# V2.net
KiCad netlist of a schematic drawn in EAGLE
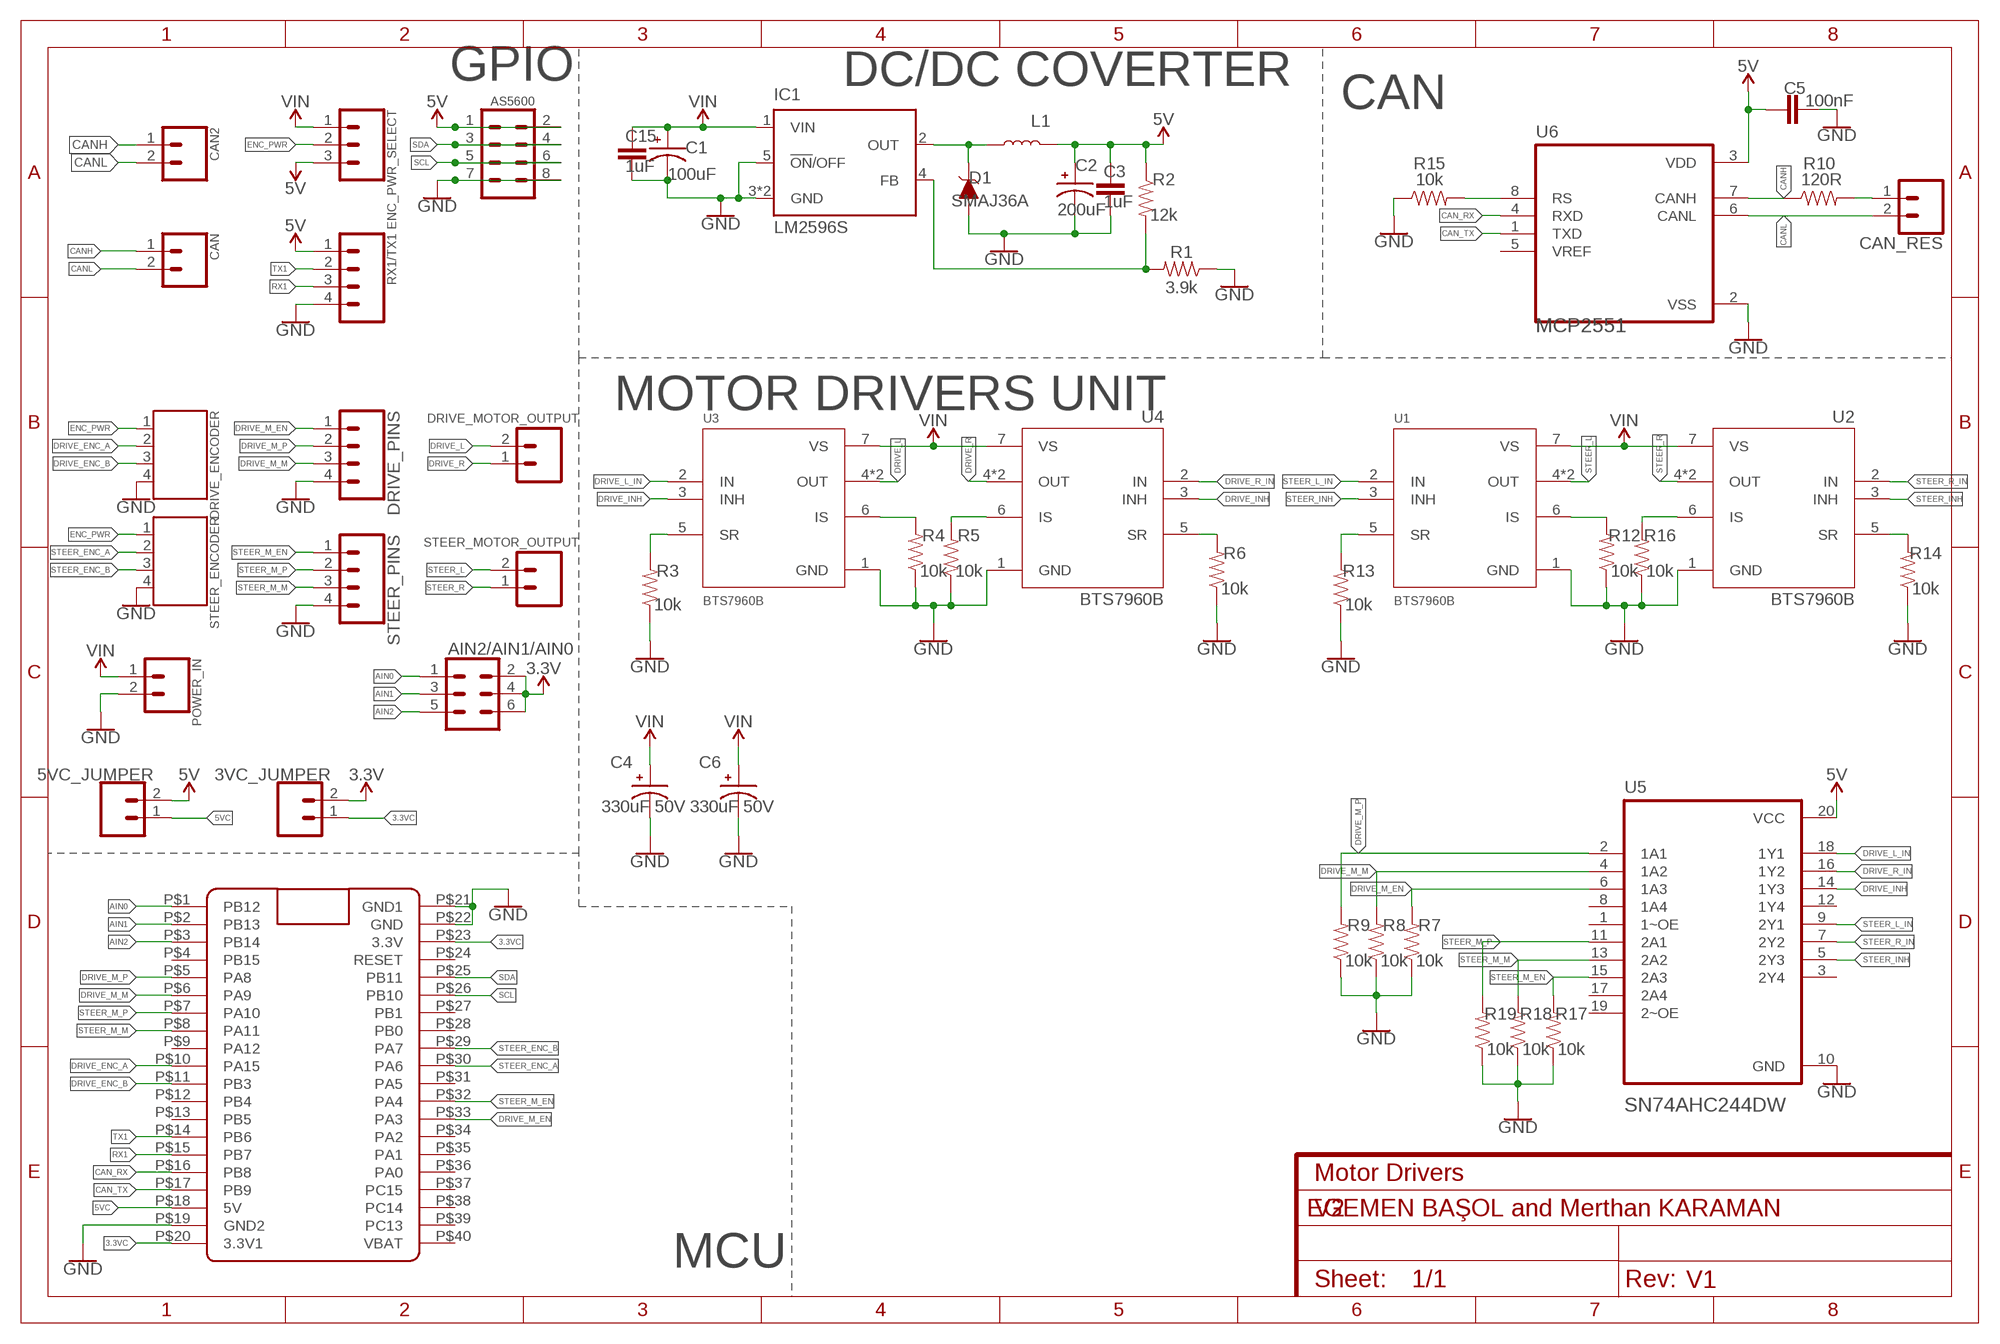
[diagram p0: schematic, sheet 1]

(export (version "E")
  (design (tool "Eeschema 10.0.6"))
  (components
    (comp (ref "3VC_JUMPER")
      (value "CONN_02")
      (footprint "eagle-import:1X02")
      (libsource (lib "eagle-import") (part "CONN_02"))
    )
    (comp (ref "5VC_JUMPER")
      (value "CONN_02")
      (footprint "eagle-import:1X02")
      (libsource (lib "eagle-import") (part "CONN_02"))
    )
    (comp (ref "AIN2/AIN1/AIN0")
      (value "CONN_03X2FEMALE")
      (footprint "eagle-import:2X3")
      (libsource (lib "eagle-import") (part "CONN_03X2FEMALE"))
    )
    (comp (ref "AS5600")
      (value "5V/SCL/SDA/GND")
      (footprint "eagle-import:2X4")
      (libsource (lib "eagle-import") (part "CONN_04X2"))
    )
    (comp (ref "C1")
      (value "100uF")
      (footprint "eagle-import:CPOL-SMD")
      (fields (field (name "MF") "Panasonic") (field (name "MP") "EEEFN1H101L"))
      (libsource (lib "eagle-import") (part "CPOL-SMD"))
    )
    (comp (ref "C2")
      (value "200uF")
      (footprint "eagle-import:CPOL-SMD")
      (fields (field (name "MF") "Panasonic") (field (name "MP") "EEEFN1H101L"))
      (libsource (lib "eagle-import") (part "CPOL-SMD"))
    )
    (comp (ref "C3")
      (value "1uF")
      (footprint "eagle-import:0603")
      (libsource (lib "eagle-import") (part "0.18UF-0603-10V-10%"))
    )
    (comp (ref "C4")
      (value "330uF 50V")
      (footprint "eagle-import:CPOL-RADIAL-5MM-10MM")
      (fields (field (name "MF") "Panasonic") (field (name "MP") "ECA2VM4R7"))
      (libsource (lib "eagle-import") (part "CPOL-RADIAL-5MM-10MM"))
    )
    (comp (ref "C5")
      (value "100nF")
      (footprint "eagle-import:0805")
      (libsource (lib "eagle-import") (part "CAP-0805"))
    )
    (comp (ref "C6")
      (value "330uF 50V")
      (footprint "eagle-import:CPOL-RADIAL-5MM-10MM")
      (fields (field (name "MF") "Panasonic") (field (name "MP") "ECA2VM4R7"))
      (libsource (lib "eagle-import") (part "CPOL-RADIAL-5MM-10MM"))
    )
    (comp (ref "C15")
      (value "1uF")
      (footprint "eagle-import:0805")
      (libsource (lib "eagle-import") (part "2.2UF-0805-25V-(+80/-20%)"))
    )
    (comp (ref "CAN")
      (value "CANH/CANL")
      (footprint "eagle-import:5.08MM_2PIN")
      (libsource (lib "eagle-import") (part "5.08MM_2PIN"))
    )
    (comp (ref "CAN2")
      (value "CANH/CANL")
      (footprint "eagle-import:5.08MM_2PIN")
      (libsource (lib "eagle-import") (part "5.08MM_2PIN"))
    )
    (comp (ref "CAN_RES")
      (value "CONN_02")
      (footprint "eagle-import:1X02")
      (libsource (lib "eagle-import") (part "CONN_02"))
    )
    (comp (ref "D1")
      (value "SMAJ36A")
      (footprint "eagle-import:DO-214AC")
      (libsource (lib "eagle-import") (part "DIODE_TVS_UNI"))
    )
    (comp (ref "DRIVE_ENCODER")
      (value "GND/B/A/PWR")
      (footprint "eagle-import:5.08MM_4PIN")
      (fields (field (name "MF") "CUI Devices") (field (name "MP") "TB006-508-04BE"))
      (libsource (lib "eagle-import") (part "5.08MM_4PIN"))
    )
    (comp (ref "DRIVE_MOTOR_OUTPUT")
      (value "5.08MM_2PIN")
      (footprint "eagle-import:5.08MM_2PIN")
      (libsource (lib "eagle-import") (part "5.08MM_2PIN"))
    )
    (comp (ref "DRIVE_PINS")
      (value "EN/ PWM_P/ PWM_M/ GND")
      (footprint "eagle-import:1X04")
      (libsource (lib "eagle-import") (part "CONN_04"))
    )
    (comp (ref "ENC_PWR_SELECT")
      (value "VIN/PWR/5V")
      (footprint "eagle-import:1X03")
      (libsource (lib "eagle-import") (part "CONN_03"))
    )
    (comp (ref "IC1")
      (value "LM2596S")
      (footprint "eagle-import:TO263-5")
      (libsource (lib "eagle-import") (part "LM2596S"))
    )
    (comp (ref "L1")
      (value "47uH")
      (footprint "eagle-import:COIL_14X14")
      (libsource (lib "eagle-import") (part "COIL"))
    )
    (comp (ref "POWER_IN")
      (value "VIN/GND")
      (footprint "eagle-import:5.08MM_2PIN")
      (libsource (lib "eagle-import") (part "5.08MM_2PIN"))
    )
    (comp (ref "R1")
      (value "3.9k")
      (footprint "eagle-import:0805")
      (libsource (lib "eagle-import") (part "RESISTOR0805"))
    )
    (comp (ref "R2")
      (value "12k")
      (footprint "eagle-import:0805")
      (libsource (lib "eagle-import") (part "RESISTOR0805"))
    )
    (comp (ref "R3")
      (value "10k")
      (footprint "eagle-import:0805")
      (libsource (lib "eagle-import") (part "RESISTOR0805"))
    )
    (comp (ref "R4")
      (value "10k")
      (footprint "eagle-import:0805")
      (libsource (lib "eagle-import") (part "RESISTOR0805"))
    )
    (comp (ref "R5")
      (value "10k")
      (footprint "eagle-import:0805")
      (libsource (lib "eagle-import") (part "RESISTOR0805"))
    )
    (comp (ref "R6")
      (value "10k")
      (footprint "eagle-import:0805")
      (libsource (lib "eagle-import") (part "RESISTOR0805"))
    )
    (comp (ref "R7")
      (value "10k")
      (footprint "eagle-import:0805")
      (libsource (lib "eagle-import") (part "RESISTOR0805"))
    )
    (comp (ref "R8")
      (value "10k")
      (footprint "eagle-import:0805")
      (libsource (lib "eagle-import") (part "RESISTOR0805"))
    )
    (comp (ref "R9")
      (value "10k")
      (footprint "eagle-import:0805")
      (libsource (lib "eagle-import") (part "RESISTOR0805"))
    )
    (comp (ref "R10")
      (value "120R")
      (footprint "eagle-import:0805")
      (libsource (lib "eagle-import") (part "RESISTOR0805"))
    )
    (comp (ref "R12")
      (value "10k")
      (footprint "eagle-import:0805")
      (libsource (lib "eagle-import") (part "RESISTOR0805"))
    )
    (comp (ref "R13")
      (value "10k")
      (footprint "eagle-import:0805")
      (libsource (lib "eagle-import") (part "RESISTOR0805"))
    )
    (comp (ref "R14")
      (value "10k")
      (footprint "eagle-import:0805")
      (libsource (lib "eagle-import") (part "RESISTOR0805"))
    )
    (comp (ref "R15")
      (value "10k")
      (footprint "eagle-import:0805")
      (libsource (lib "eagle-import") (part "RESISTOR0805"))
    )
    (comp (ref "R16")
      (value "10k")
      (footprint "eagle-import:0805")
      (libsource (lib "eagle-import") (part "RESISTOR0805"))
    )
    (comp (ref "R17")
      (value "10k")
      (footprint "eagle-import:0805")
      (libsource (lib "eagle-import") (part "RESISTOR0805"))
    )
    (comp (ref "R18")
      (value "10k")
      (footprint "eagle-import:0805")
      (libsource (lib "eagle-import") (part "RESISTOR0805"))
    )
    (comp (ref "R19")
      (value "10k")
      (footprint "eagle-import:0805")
      (libsource (lib "eagle-import") (part "RESISTOR0805"))
    )
    (comp (ref "RX1/TX1")
      (value "GND/RX1/TX1/5V")
      (footprint "eagle-import:1X04")
      (libsource (lib "eagle-import") (part "CONN_04"))
    )
    (comp (ref "STEER_ENCODER")
      (value "PWR/A/B/GND")
      (footprint "eagle-import:5.08MM_4PIN")
      (fields (field (name "MF") "CUI Devices") (field (name "MP") "TB006-508-04BE"))
      (libsource (lib "eagle-import") (part "5.08MM_4PIN"))
    )
    (comp (ref "STEER_MOTOR_OUTPUT")
      (value "5.08MM_2PIN")
      (footprint "eagle-import:5.08MM_2PIN")
      (libsource (lib "eagle-import") (part "5.08MM_2PIN"))
    )
    (comp (ref "STEER_PINS")
      (value "EN/ PWM_P/ PWM_M/ GND")
      (footprint "eagle-import:1X04")
      (libsource (lib "eagle-import") (part "CONN_04"))
    )
    (comp (ref "U$1")
      (value "BLUE_PILL")
      (footprint "eagle-import:BLUE_PILL")
      (libsource (lib "eagle-import") (part "BLUE_PILL"))
    )
    (comp (ref "U1")
      (value "BTS7960B")
      (footprint "eagle-import:DPAK127P1490X440-8N")
      (libsource (lib "eagle-import") (part "BTS7960B"))
    )
    (comp (ref "U2")
      (value "BTS7960B")
      (footprint "eagle-import:DPAK127P1490X440-8N")
      (libsource (lib "eagle-import") (part "BTS7960B"))
    )
    (comp (ref "U3")
      (value "BTS7960B")
      (footprint "eagle-import:DPAK127P1490X440-8N")
      (libsource (lib "eagle-import") (part "BTS7960B"))
    )
    (comp (ref "U4")
      (value "BTS7960B")
      (footprint "eagle-import:DPAK127P1490X440-8N")
      (libsource (lib "eagle-import") (part "BTS7960B"))
    )
    (comp (ref "U5")
      (value "SN74AHC244DW")
      (footprint "eagle-import:SOIC127P1030X265-20N")
      (fields (field (name "MF") "Texas Instruments"))
      (libsource (lib "eagle-import") (part "SN74AHC244DW"))
    )
    (comp (ref "U6")
      (value "MCP2551")
      (footprint "eagle-import:DIP-8")
      (fields (field (name "MF") "Microchip") (field (name "MP") "MCP2551-E/P"))
      (libsource (lib "eagle-import") (part "MCP2551"))
    )
  )
  (nets
    (net (code "1") (name "3.3V") (class "Default")
      (node (ref "3VC_JUMPER") (pin "2") (pinfunction "2_2") (pintype "passive"))
      (node (ref "AIN2/AIN1/AIN0") (pin "2") (pinfunction "2_2") (pintype "bidirectional"))
      (node (ref "AIN2/AIN1/AIN0") (pin "4") (pinfunction "4_4") (pintype "bidirectional"))
      (node (ref "AIN2/AIN1/AIN0") (pin "6") (pinfunction "6_6") (pintype "bidirectional"))
    )
    (net (code "2") (name "3.3VC") (class "Default")
      (node (ref "3VC_JUMPER") (pin "1") (pinfunction "1_1") (pintype "passive"))
      (node (ref "U$1") (pin "P$20") (pinfunction "3.3V1_P$20") (pintype "bidirectional"))
      (node (ref "U$1") (pin "P$23") (pinfunction "3.3V_P$23") (pintype "bidirectional"))
    )
    (net (code "3") (name "5V") (class "Default")
      (node (ref "5VC_JUMPER") (pin "2") (pinfunction "2_2") (pintype "passive"))
      (node (ref "AS5600") (pin "1") (pinfunction "1_1") (pintype "passive"))
      (node (ref "AS5600") (pin "2") (pinfunction "2_2") (pintype "passive"))
      (node (ref "C2") (pin "1") (pinfunction "1_1") (pintype "passive"))
      (node (ref "C3") (pin "2") (pinfunction "2_2") (pintype "passive"))
      (node (ref "C5") (pin "2") (pinfunction "2_2") (pintype "passive"))
      (node (ref "ENC_PWR_SELECT") (pin "3") (pinfunction "3_3") (pintype "passive"))
      (node (ref "L1") (pin "P$2") (pinfunction "2_P$2") (pintype "passive"))
      (node (ref "R2") (pin "1") (pinfunction "1_1") (pintype "passive"))
      (node (ref "RX1/TX1") (pin "1") (pinfunction "1_1") (pintype "passive"))
      (node (ref "U5") (pin "20") (pinfunction "VCC_20") (pintype "power_in"))
      (node (ref "U6") (pin "3") (pinfunction "VDD_3") (pintype "power_in"))
    )
    (net (code "4") (name "5VC") (class "Default")
      (node (ref "5VC_JUMPER") (pin "1") (pinfunction "1_1") (pintype "passive"))
      (node (ref "U$1") (pin "P$18") (pinfunction "5V_P$18") (pintype "bidirectional"))
    )
    (net (code "5") (name "AIN0") (class "Default")
      (node (ref "AIN2/AIN1/AIN0") (pin "1") (pinfunction "1_1") (pintype "bidirectional"))
      (node (ref "U$1") (pin "P$1") (pinfunction "PB12_P$1") (pintype "bidirectional"))
    )
    (net (code "6") (name "AIN1") (class "Default")
      (node (ref "AIN2/AIN1/AIN0") (pin "3") (pinfunction "3_3") (pintype "bidirectional"))
      (node (ref "U$1") (pin "P$2") (pinfunction "PB13_P$2") (pintype "bidirectional"))
    )
    (net (code "7") (name "AIN2") (class "Default")
      (node (ref "AIN2/AIN1/AIN0") (pin "5") (pinfunction "5_5") (pintype "bidirectional"))
      (node (ref "U$1") (pin "P$3") (pinfunction "PB14_P$3") (pintype "bidirectional"))
    )
    (net (code "8") (name "CANH") (class "Default")
      (node (ref "CAN") (pin "1") (pinfunction "1_1") (pintype "passive"))
      (node (ref "CAN2") (pin "1") (pinfunction "1_1") (pintype "passive"))
      (node (ref "R10") (pin "1") (pinfunction "1_1") (pintype "passive"))
      (node (ref "U6") (pin "7") (pinfunction "CANH_7") (pintype "output"))
    )
    (net (code "9") (name "CANL") (class "Default")
      (node (ref "CAN") (pin "2") (pinfunction "2_2") (pintype "passive"))
      (node (ref "CAN2") (pin "2") (pinfunction "2_2") (pintype "passive"))
      (node (ref "CAN_RES") (pin "2") (pinfunction "2_2") (pintype "passive"))
      (node (ref "U6") (pin "6") (pinfunction "CANL_6") (pintype "output"))
    )
    (net (code "10") (name "CAN_RX") (class "Default")
      (node (ref "U$1") (pin "P$16") (pinfunction "PB8_P$16") (pintype "bidirectional"))
      (node (ref "U6") (pin "4") (pinfunction "RXD_4") (pintype "input"))
    )
    (net (code "11") (name "CAN_TX") (class "Default")
      (node (ref "U$1") (pin "P$17") (pinfunction "PB9_P$17") (pintype "bidirectional"))
      (node (ref "U6") (pin "1") (pinfunction "TXD_1") (pintype "input"))
    )
    (net (code "12") (name "DRIVE_ENC_A") (class "Default")
      (node (ref "DRIVE_ENCODER") (pin "2") (pinfunction "2_2") (pintype "passive"))
      (node (ref "U$1") (pin "P$10") (pinfunction "PA15_P$10") (pintype "bidirectional"))
    )
    (net (code "13") (name "DRIVE_ENC_B") (class "Default")
      (node (ref "DRIVE_ENCODER") (pin "3") (pinfunction "3_3") (pintype "passive"))
      (node (ref "U$1") (pin "P$11") (pinfunction "PB3_P$11") (pintype "bidirectional"))
    )
    (net (code "14") (name "DRIVE_INH") (class "Default")
      (node (ref "U3") (pin "3") (pinfunction "INH_3") (pintype "input"))
      (node (ref "U4") (pin "3") (pinfunction "INH_3") (pintype "input"))
      (node (ref "U5") (pin "14") (pinfunction "1Y3_14") (pintype "output"))
    )
    (net (code "15") (name "DRIVE_L") (class "Default")
      (node (ref "DRIVE_MOTOR_OUTPUT") (pin "2") (pinfunction "2_2") (pintype "passive"))
      (node (ref "U3") (pin "4") (pinfunction "OUT_4") (pintype "output"))
      (node (ref "U3") (pin "8") (pinfunction "OUT_8") (pintype "output"))
    )
    (net (code "16") (name "DRIVE_L_IN") (class "Default")
      (node (ref "U3") (pin "2") (pinfunction "IN_2") (pintype "input"))
      (node (ref "U5") (pin "18") (pinfunction "1Y1_18") (pintype "output"))
    )
    (net (code "17") (name "DRIVE_M_EN") (class "Default")
      (node (ref "DRIVE_PINS") (pin "1") (pinfunction "1_1") (pintype "passive"))
      (node (ref "R7") (pin "2") (pinfunction "2_2") (pintype "passive"))
      (node (ref "U$1") (pin "P$33") (pinfunction "PA3_P$33") (pintype "bidirectional"))
      (node (ref "U5") (pin "6") (pinfunction "1A3_6") (pintype "input"))
    )
    (net (code "18") (name "DRIVE_M_M") (class "Default")
      (node (ref "DRIVE_PINS") (pin "3") (pinfunction "3_3") (pintype "passive"))
      (node (ref "R8") (pin "2") (pinfunction "2_2") (pintype "passive"))
      (node (ref "U$1") (pin "P$6") (pinfunction "PA9_P$6") (pintype "bidirectional"))
      (node (ref "U5") (pin "4") (pinfunction "1A2_4") (pintype "input"))
    )
    (net (code "19") (name "DRIVE_M_P") (class "Default")
      (node (ref "DRIVE_PINS") (pin "2") (pinfunction "2_2") (pintype "passive"))
      (node (ref "R9") (pin "2") (pinfunction "2_2") (pintype "passive"))
      (node (ref "U$1") (pin "P$5") (pinfunction "PA8_P$5") (pintype "bidirectional"))
      (node (ref "U5") (pin "2") (pinfunction "1A1_2") (pintype "input"))
    )
    (net (code "20") (name "DRIVE_R") (class "Default")
      (node (ref "DRIVE_MOTOR_OUTPUT") (pin "1") (pinfunction "1_1") (pintype "passive"))
      (node (ref "U4") (pin "4") (pinfunction "OUT_4") (pintype "output"))
      (node (ref "U4") (pin "8") (pinfunction "OUT_8") (pintype "output"))
    )
    (net (code "21") (name "DRIVE_R_IN") (class "Default")
      (node (ref "U4") (pin "2") (pinfunction "IN_2") (pintype "input"))
      (node (ref "U5") (pin "16") (pinfunction "1Y2_16") (pintype "output"))
    )
    (net (code "22") (name "ENC_PWR") (class "Default")
      (node (ref "DRIVE_ENCODER") (pin "1") (pinfunction "1_1") (pintype "passive"))
      (node (ref "ENC_PWR_SELECT") (pin "2") (pinfunction "2_2") (pintype "passive"))
      (node (ref "STEER_ENCODER") (pin "1") (pinfunction "1_1") (pintype "passive"))
    )
    (net (code "23") (name "GND") (class "Default")
      (node (ref "AS5600") (pin "7") (pinfunction "7_7") (pintype "passive"))
      (node (ref "AS5600") (pin "8") (pinfunction "8_8") (pintype "passive"))
      (node (ref "C1") (pin "2") (pinfunction "2_2") (pintype "passive"))
      (node (ref "C15") (pin "1") (pinfunction "1_1") (pintype "passive"))
      (node (ref "C2") (pin "2") (pinfunction "2_2") (pintype "passive"))
      (node (ref "C3") (pin "1") (pinfunction "1_1") (pintype "passive"))
      (node (ref "C4") (pin "N") (pinfunction "N_N") (pintype "passive"))
      (node (ref "C5") (pin "1") (pinfunction "1_1") (pintype "passive"))
      (node (ref "C6") (pin "N") (pinfunction "N_N") (pintype "passive"))
      (node (ref "D1") (pin "A") (pinfunction "A_A") (pintype "passive"))
      (node (ref "DRIVE_ENCODER") (pin "4") (pinfunction "4_4") (pintype "passive"))
      (node (ref "DRIVE_PINS") (pin "4") (pinfunction "4_4") (pintype "passive"))
      (node (ref "IC1") (pin "3") (pinfunction "GND_3") (pintype "power_in"))
      (node (ref "IC1") (pin "5") (pinfunction "~{ON}/OFF_5") (pintype "input"))
      (node (ref "IC1") (pin "TAB") (pinfunction "GND_TAB") (pintype "power_in"))
      (node (ref "POWER_IN") (pin "2") (pinfunction "2_2") (pintype "passive"))
      (node (ref "R1") (pin "1") (pinfunction "1_1") (pintype "passive"))
      (node (ref "R12") (pin "1") (pinfunction "1_1") (pintype "passive"))
      (node (ref "R13") (pin "1") (pinfunction "1_1") (pintype "passive"))
      (node (ref "R14") (pin "1") (pinfunction "1_1") (pintype "passive"))
      (node (ref "R15") (pin "1") (pinfunction "1_1") (pintype "passive"))
      (node (ref "R16") (pin "1") (pinfunction "1_1") (pintype "passive"))
      (node (ref "R17") (pin "1") (pinfunction "1_1") (pintype "passive"))
      (node (ref "R18") (pin "1") (pinfunction "1_1") (pintype "passive"))
      (node (ref "R19") (pin "1") (pinfunction "1_1") (pintype "passive"))
      (node (ref "R3") (pin "1") (pinfunction "1_1") (pintype "passive"))
      (node (ref "R4") (pin "1") (pinfunction "1_1") (pintype "passive"))
      (node (ref "R5") (pin "1") (pinfunction "1_1") (pintype "passive"))
      (node (ref "R6") (pin "1") (pinfunction "1_1") (pintype "passive"))
      (node (ref "R7") (pin "1") (pinfunction "1_1") (pintype "passive"))
      (node (ref "R8") (pin "1") (pinfunction "1_1") (pintype "passive"))
      (node (ref "R9") (pin "1") (pinfunction "1_1") (pintype "passive"))
      (node (ref "RX1/TX1") (pin "4") (pinfunction "4_4") (pintype "passive"))
      (node (ref "STEER_ENCODER") (pin "4") (pinfunction "4_4") (pintype "passive"))
      (node (ref "STEER_PINS") (pin "4") (pinfunction "4_4") (pintype "passive"))
      (node (ref "U$1") (pin "P$19") (pinfunction "GND2_P$19") (pintype "bidirectional"))
      (node (ref "U$1") (pin "P$21") (pinfunction "GND1_P$21") (pintype "power_in"))
      (node (ref "U$1") (pin "P$22") (pinfunction "GND_P$22") (pintype "bidirectional"))
      (node (ref "U1") (pin "1") (pinfunction "GND_1") (pintype "power_in"))
      (node (ref "U2") (pin "1") (pinfunction "GND_1") (pintype "power_in"))
      (node (ref "U3") (pin "1") (pinfunction "GND_1") (pintype "power_in"))
      (node (ref "U4") (pin "1") (pinfunction "GND_1") (pintype "power_in"))
      (node (ref "U5") (pin "10") (pinfunction "GND_10") (pintype "power_in"))
      (node (ref "U6") (pin "2") (pinfunction "VSS_2") (pintype "power_in"))
    )
    (net (code "24") (name "Net-(CAN_RES-Pad1)") (class "Default")
      (node (ref "CAN_RES") (pin "1") (pinfunction "1_1") (pintype "passive"))
      (node (ref "R10") (pin "2") (pinfunction "2_2") (pintype "passive"))
    )
    (net (code "25") (name "Net-(IC1-FB)") (class "Default")
      (node (ref "IC1") (pin "4") (pinfunction "FB_4") (pintype "input"))
      (node (ref "R1") (pin "2") (pinfunction "2_2") (pintype "passive"))
      (node (ref "R2") (pin "2") (pinfunction "2_2") (pintype "passive"))
    )
    (net (code "26") (name "Net-(IC1-OUT)") (class "Default")
      (node (ref "D1") (pin "C") (pinfunction "C_C") (pintype "passive"))
      (node (ref "IC1") (pin "2") (pinfunction "OUT_2") (pintype "output"))
      (node (ref "L1") (pin "P$1") (pinfunction "1_P$1") (pintype "passive"))
    )
    (net (code "27") (name "Net-(U1-IS)") (class "Default")
      (node (ref "R12") (pin "2") (pinfunction "2_2") (pintype "passive"))
      (node (ref "U1") (pin "6") (pinfunction "IS_6") (pintype "output"))
    )
    (net (code "28") (name "Net-(U1-SR)") (class "Default")
      (node (ref "R13") (pin "2") (pinfunction "2_2") (pintype "passive"))
      (node (ref "U1") (pin "5") (pinfunction "SR_5") (pintype "input"))
    )
    (net (code "29") (name "Net-(U2-IS)") (class "Default")
      (node (ref "R16") (pin "2") (pinfunction "2_2") (pintype "passive"))
      (node (ref "U2") (pin "6") (pinfunction "IS_6") (pintype "output"))
    )
    (net (code "30") (name "Net-(U2-SR)") (class "Default")
      (node (ref "R14") (pin "2") (pinfunction "2_2") (pintype "passive"))
      (node (ref "U2") (pin "5") (pinfunction "SR_5") (pintype "input"))
    )
    (net (code "31") (name "Net-(U3-IS)") (class "Default")
      (node (ref "R4") (pin "2") (pinfunction "2_2") (pintype "passive"))
      (node (ref "U3") (pin "6") (pinfunction "IS_6") (pintype "output"))
    )
    (net (code "32") (name "Net-(U3-SR)") (class "Default")
      (node (ref "R3") (pin "2") (pinfunction "2_2") (pintype "passive"))
      (node (ref "U3") (pin "5") (pinfunction "SR_5") (pintype "input"))
    )
    (net (code "33") (name "Net-(U4-IS)") (class "Default")
      (node (ref "R5") (pin "2") (pinfunction "2_2") (pintype "passive"))
      (node (ref "U4") (pin "6") (pinfunction "IS_6") (pintype "output"))
    )
    (net (code "34") (name "Net-(U4-SR)") (class "Default")
      (node (ref "R6") (pin "2") (pinfunction "2_2") (pintype "passive"))
      (node (ref "U4") (pin "5") (pinfunction "SR_5") (pintype "input"))
    )
    (net (code "35") (name "Net-(U6-RS)") (class "Default")
      (node (ref "R15") (pin "2") (pinfunction "2_2") (pintype "passive"))
      (node (ref "U6") (pin "8") (pinfunction "RS_8") (pintype "input"))
    )
    (net (code "36") (name "RX1") (class "Default")
      (node (ref "RX1/TX1") (pin "3") (pinfunction "3_3") (pintype "passive"))
      (node (ref "U$1") (pin "P$15") (pinfunction "PB7_P$15") (pintype "bidirectional"))
    )
    (net (code "37") (name "SCL") (class "Default")
      (node (ref "AS5600") (pin "5") (pinfunction "5_5") (pintype "passive"))
      (node (ref "AS5600") (pin "6") (pinfunction "6_6") (pintype "passive"))
      (node (ref "U$1") (pin "P$26") (pinfunction "PB10_P$26") (pintype "bidirectional"))
    )
    (net (code "38") (name "SDA") (class "Default")
      (node (ref "AS5600") (pin "3") (pinfunction "3_3") (pintype "passive"))
      (node (ref "AS5600") (pin "4") (pinfunction "4_4") (pintype "passive"))
      (node (ref "U$1") (pin "P$25") (pinfunction "PB11_P$25") (pintype "bidirectional"))
    )
    (net (code "39") (name "STEER_ENC_A") (class "Default")
      (node (ref "STEER_ENCODER") (pin "2") (pinfunction "2_2") (pintype "passive"))
      (node (ref "U$1") (pin "P$30") (pinfunction "PA6_P$30") (pintype "bidirectional"))
    )
    (net (code "40") (name "STEER_ENC_B") (class "Default")
      (node (ref "STEER_ENCODER") (pin "3") (pinfunction "3_3") (pintype "passive"))
      (node (ref "U$1") (pin "P$29") (pinfunction "PA7_P$29") (pintype "bidirectional"))
    )
    (net (code "41") (name "STEER_INH") (class "Default")
      (node (ref "U1") (pin "3") (pinfunction "INH_3") (pintype "input"))
      (node (ref "U2") (pin "3") (pinfunction "INH_3") (pintype "input"))
      (node (ref "U5") (pin "5") (pinfunction "2Y3_5") (pintype "output"))
    )
    (net (code "42") (name "STEER_L") (class "Default")
      (node (ref "STEER_MOTOR_OUTPUT") (pin "2") (pinfunction "2_2") (pintype "passive"))
      (node (ref "U1") (pin "4") (pinfunction "OUT_4") (pintype "output"))
      (node (ref "U1") (pin "8") (pinfunction "OUT_8") (pintype "output"))
    )
    (net (code "43") (name "STEER_L_IN") (class "Default")
      (node (ref "U1") (pin "2") (pinfunction "IN_2") (pintype "input"))
      (node (ref "U5") (pin "9") (pinfunction "2Y1_9") (pintype "output"))
    )
    (net (code "44") (name "STEER_M_EN") (class "Default")
      (node (ref "R17") (pin "2") (pinfunction "2_2") (pintype "passive"))
      (node (ref "STEER_PINS") (pin "1") (pinfunction "1_1") (pintype "passive"))
      (node (ref "U$1") (pin "P$32") (pinfunction "PA4_P$32") (pintype "bidirectional"))
      (node (ref "U5") (pin "15") (pinfunction "2A3_15") (pintype "input"))
    )
    (net (code "45") (name "STEER_M_M") (class "Default")
      (node (ref "R18") (pin "2") (pinfunction "2_2") (pintype "passive"))
      (node (ref "STEER_PINS") (pin "3") (pinfunction "3_3") (pintype "passive"))
      (node (ref "U$1") (pin "P$8") (pinfunction "PA11_P$8") (pintype "bidirectional"))
      (node (ref "U5") (pin "13") (pinfunction "2A2_13") (pintype "input"))
    )
    (net (code "46") (name "STEER_M_P") (class "Default")
      (node (ref "R19") (pin "2") (pinfunction "2_2") (pintype "passive"))
      (node (ref "STEER_PINS") (pin "2") (pinfunction "2_2") (pintype "passive"))
      (node (ref "U$1") (pin "P$7") (pinfunction "PA10_P$7") (pintype "bidirectional"))
      (node (ref "U5") (pin "11") (pinfunction "2A1_11") (pintype "input"))
    )
    (net (code "47") (name "STEER_R") (class "Default")
      (node (ref "STEER_MOTOR_OUTPUT") (pin "1") (pinfunction "1_1") (pintype "passive"))
      (node (ref "U2") (pin "4") (pinfunction "OUT_4") (pintype "output"))
      (node (ref "U2") (pin "8") (pinfunction "OUT_8") (pintype "output"))
    )
    (net (code "48") (name "STEER_R_IN") (class "Default")
      (node (ref "U2") (pin "2") (pinfunction "IN_2") (pintype "input"))
      (node (ref "U5") (pin "7") (pinfunction "2Y2_7") (pintype "output"))
    )
    (net (code "49") (name "TX1") (class "Default")
      (node (ref "RX1/TX1") (pin "2") (pinfunction "2_2") (pintype "passive"))
      (node (ref "U$1") (pin "P$14") (pinfunction "PB6_P$14") (pintype "bidirectional"))
    )
    (net (code "50") (name "VIN") (class "Default")
      (node (ref "C1") (pin "1") (pinfunction "1_1") (pintype "passive"))
      (node (ref "C15") (pin "2") (pinfunction "2_2") (pintype "passive"))
      (node (ref "C4") (pin "P") (pinfunction "P_P") (pintype "passive"))
      (node (ref "C6") (pin "P") (pinfunction "P_P") (pintype "passive"))
      (node (ref "ENC_PWR_SELECT") (pin "1") (pinfunction "1_1") (pintype "passive"))
      (node (ref "IC1") (pin "1") (pinfunction "VIN_1") (pintype "input"))
      (node (ref "POWER_IN") (pin "1") (pinfunction "1_1") (pintype "passive"))
      (node (ref "U1") (pin "7") (pinfunction "VS_7") (pintype "power_in"))
      (node (ref "U2") (pin "7") (pinfunction "VS_7") (pintype "power_in"))
      (node (ref "U3") (pin "7") (pinfunction "VS_7") (pintype "power_in"))
      (node (ref "U4") (pin "7") (pinfunction "VS_7") (pintype "power_in"))
    )
    (net (code "51") (name "unconnected-(U$1-PA0-PadP$36)") (class "Default")
      (node (ref "U$1") (pin "P$36") (pinfunction "PA0_P$36") (pintype "bidirectional"))
    )
    (net (code "52") (name "unconnected-(U$1-PA1-PadP$35)") (class "Default")
      (node (ref "U$1") (pin "P$35") (pinfunction "PA1_P$35") (pintype "bidirectional"))
    )
    (net (code "53") (name "unconnected-(U$1-PA2-PadP$34)") (class "Default")
      (node (ref "U$1") (pin "P$34") (pinfunction "PA2_P$34") (pintype "bidirectional"))
    )
    (net (code "54") (name "unconnected-(U$1-PA5-PadP$31)") (class "Default")
      (node (ref "U$1") (pin "P$31") (pinfunction "PA5_P$31") (pintype "bidirectional"))
    )
    (net (code "55") (name "unconnected-(U$1-PA12-PadP$9)") (class "Default")
      (node (ref "U$1") (pin "P$9") (pinfunction "PA12_P$9") (pintype "bidirectional"))
    )
    (net (code "56") (name "unconnected-(U$1-PB0-PadP$28)") (class "Default")
      (node (ref "U$1") (pin "P$28") (pinfunction "PB0_P$28") (pintype "bidirectional"))
    )
    (net (code "57") (name "unconnected-(U$1-PB1-PadP$27)") (class "Default")
      (node (ref "U$1") (pin "P$27") (pinfunction "PB1_P$27") (pintype "bidirectional"))
    )
    (net (code "58") (name "unconnected-(U$1-PB4-PadP$12)") (class "Default")
      (node (ref "U$1") (pin "P$12") (pinfunction "PB4_P$12") (pintype "bidirectional"))
    )
    (net (code "59") (name "unconnected-(U$1-PB5-PadP$13)") (class "Default")
      (node (ref "U$1") (pin "P$13") (pinfunction "PB5_P$13") (pintype "bidirectional"))
    )
    (net (code "60") (name "unconnected-(U$1-PB15-PadP$4)") (class "Default")
      (node (ref "U$1") (pin "P$4") (pinfunction "PB15_P$4") (pintype "bidirectional"))
    )
    (net (code "61") (name "unconnected-(U$1-PC13-PadP$39)") (class "Default")
      (node (ref "U$1") (pin "P$39") (pinfunction "PC13_P$39") (pintype "bidirectional"))
    )
    (net (code "62") (name "unconnected-(U$1-PC14-PadP$38)") (class "Default")
      (node (ref "U$1") (pin "P$38") (pinfunction "PC14_P$38") (pintype "bidirectional"))
    )
    (net (code "63") (name "unconnected-(U$1-PC15-PadP$37)") (class "Default")
      (node (ref "U$1") (pin "P$37") (pinfunction "PC15_P$37") (pintype "bidirectional"))
    )
    (net (code "64") (name "unconnected-(U$1-RESET-PadP$24)") (class "Default")
      (node (ref "U$1") (pin "P$24") (pinfunction "RESET_P$24") (pintype "bidirectional"))
    )
    (net (code "65") (name "unconnected-(U$1-VBAT-PadP$40)") (class "Default")
      (node (ref "U$1") (pin "P$40") (pinfunction "VBAT_P$40") (pintype "bidirectional"))
    )
    (net (code "66") (name "unconnected-(U5-1A4-Pad8)") (class "Default")
      (node (ref "U5") (pin "8") (pinfunction "1A4_8") (pintype "input"))
    )
    (net (code "67") (name "unconnected-(U5-1Y4-Pad12)") (class "Default")
      (node (ref "U5") (pin "12") (pinfunction "1Y4_12") (pintype "output"))
    )
    (net (code "68") (name "unconnected-(U5-1~{OE}-Pad1)") (class "Default")
      (node (ref "U5") (pin "1") (pinfunction "1~{OE}_1") (pintype "input"))
    )
    (net (code "69") (name "unconnected-(U5-2A4-Pad17)") (class "Default")
      (node (ref "U5") (pin "17") (pinfunction "2A4_17") (pintype "input"))
    )
    (net (code "70") (name "unconnected-(U5-2Y4-Pad3)") (class "Default")
      (node (ref "U5") (pin "3") (pinfunction "2Y4_3") (pintype "output"))
    )
    (net (code "71") (name "unconnected-(U5-2~{OE}-Pad19)") (class "Default")
      (node (ref "U5") (pin "19") (pinfunction "2~{OE}_19") (pintype "input"))
    )
    (net (code "72") (name "unconnected-(U6-VREF-Pad5)") (class "Default")
      (node (ref "U6") (pin "5") (pinfunction "VREF_5") (pintype "input"))
    )
  )
)
